# ECG-EEG.net
KiCad netlist of a schematic drawn in EAGLE
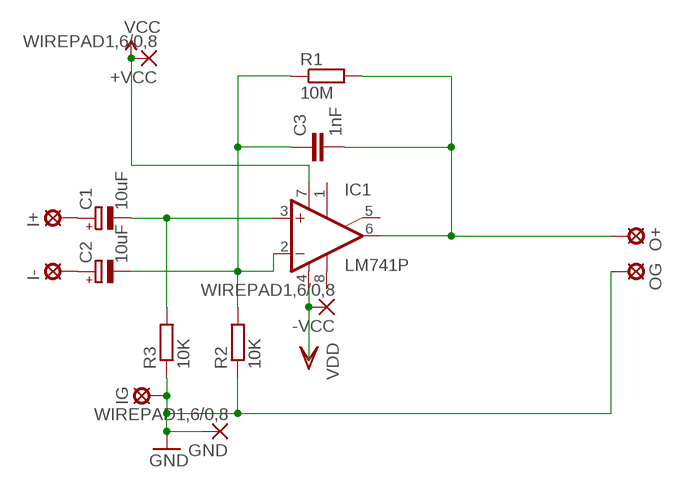
[diagram p0: schematic, sheet 1]

(export (version "E")
  (design (tool "Eeschema 10.0.6"))
  (components
    (comp (ref "+VCC")
      (value "WIREPAD1,6/0,8")
      (footprint "eagle-import:1,6_0,8")
      (libsource (lib "eagle-import") (part "WIREPAD1,6/0,8"))
    )
    (comp (ref "-VCC")
      (value "WIREPAD1,6/0,8")
      (footprint "eagle-import:1,6_0,8")
      (libsource (lib "eagle-import") (part "WIREPAD1,6/0,8"))
    )
    (comp (ref "C1")
      (value "10uF")
      (footprint "eagle-import:E1,8-4")
      (libsource (lib "eagle-import") (part "CPOL-EUE1.8-4"))
    )
    (comp (ref "C2")
      (value "10uF")
      (footprint "eagle-import:E1,8-4")
      (libsource (lib "eagle-import") (part "CPOL-EUE1.8-4"))
    )
    (comp (ref "C3")
      (value "1nF")
      (footprint "eagle-import:C025-025X050")
      (libsource (lib "eagle-import") (part "C-EU025-025X050"))
    )
    (comp (ref "GND")
      (value "WIREPAD1,6/0,8")
      (footprint "eagle-import:1,6_0,8")
      (libsource (lib "eagle-import") (part "WIREPAD1,6/0,8"))
    )
    (comp (ref "I+")
      (value "LSP10")
      (footprint "eagle-import:LSP10")
      (libsource (lib "eagle-import") (part "LSP10"))
    )
    (comp (ref "I-")
      (value "LSP10")
      (footprint "eagle-import:LSP10")
      (libsource (lib "eagle-import") (part "LSP10"))
    )
    (comp (ref "IC1")
      (value "LM741P")
      (footprint "eagle-import:DIL08")
      (libsource (lib "eagle-import") (part "741PLM"))
    )
    (comp (ref "IG")
      (value "LSP10")
      (footprint "eagle-import:LSP10")
      (libsource (lib "eagle-import") (part "LSP10"))
    )
    (comp (ref "O+")
      (value "LSP10")
      (footprint "eagle-import:LSP10")
      (libsource (lib "eagle-import") (part "LSP10"))
    )
    (comp (ref "OG")
      (value "LSP10")
      (footprint "eagle-import:LSP10")
      (libsource (lib "eagle-import") (part "LSP10"))
    )
    (comp (ref "R1")
      (value "10M")
      (footprint "eagle-import:0204_7")
      (libsource (lib "eagle-import") (part "R-EU_0204/7"))
    )
    (comp (ref "R2")
      (value "10K")
      (footprint "eagle-import:0204_7")
      (libsource (lib "eagle-import") (part "R-EU_0204/7"))
    )
    (comp (ref "R3")
      (value "10K")
      (footprint "eagle-import:0204_7")
      (libsource (lib "eagle-import") (part "R-EU_0204/7"))
    )
  )
  (nets
    (net (code "1") (name "GND") (class "Default")
      (node (ref "GND") (pin "1") (pinfunction "P_1") (pintype "passive"))
      (node (ref "IG") (pin "MP") (pinfunction "MP_MP") (pintype "passive"))
      (node (ref "OG") (pin "MP") (pinfunction "MP_MP") (pintype "passive"))
      (node (ref "R2") (pin "1") (pinfunction "1_1") (pintype "passive"))
      (node (ref "R3") (pin "1") (pinfunction "1_1") (pintype "passive"))
    )
    (net (code "2") (name "Net-(-VCC-P)") (class "Default")
      (node (ref "-VCC") (pin "1") (pinfunction "P_1") (pintype "passive"))
      (node (ref "IC1") (pin "4") (pinfunction "V-_4") (pintype "power_in"))
    )
    (net (code "3") (name "Net-(C1-Pad+)") (class "Default")
      (node (ref "C1") (pin "+") (pinfunction "+_+") (pintype "passive"))
      (node (ref "I+") (pin "MP") (pinfunction "MP_MP") (pintype "passive"))
    )
    (net (code "4") (name "Net-(C2-Pad+)") (class "Default")
      (node (ref "C2") (pin "+") (pinfunction "+_+") (pintype "passive"))
      (node (ref "I-") (pin "MP") (pinfunction "MP_MP") (pintype "passive"))
    )
    (net (code "5") (name "Net-(IC1-+IN)") (class "Default")
      (node (ref "C1") (pin "-") (pinfunction "-_-") (pintype "passive"))
      (node (ref "IC1") (pin "3") (pinfunction "+IN_3") (pintype "input"))
      (node (ref "R3") (pin "2") (pinfunction "2_2") (pintype "passive"))
    )
    (net (code "6") (name "Net-(IC1--IN)") (class "Default")
      (node (ref "C2") (pin "-") (pinfunction "-_-") (pintype "passive"))
      (node (ref "C3") (pin "1") (pinfunction "1_1") (pintype "passive"))
      (node (ref "IC1") (pin "2") (pinfunction "-IN_2") (pintype "input"))
      (node (ref "R1") (pin "1") (pinfunction "1_1") (pintype "passive"))
      (node (ref "R2") (pin "2") (pinfunction "2_2") (pintype "passive"))
    )
    (net (code "7") (name "Net-(IC1-OUT)") (class "Default")
      (node (ref "C3") (pin "2") (pinfunction "2_2") (pintype "passive"))
      (node (ref "IC1") (pin "6") (pinfunction "OUT_6") (pintype "output"))
      (node (ref "O+") (pin "MP") (pinfunction "MP_MP") (pintype "passive"))
      (node (ref "R1") (pin "2") (pinfunction "2_2") (pintype "passive"))
    )
    (net (code "8") (name "VCC") (class "Default")
      (node (ref "+VCC") (pin "1") (pinfunction "P_1") (pintype "passive"))
      (node (ref "IC1") (pin "7") (pinfunction "V+_7") (pintype "power_in"))
    )
    (net (code "10") (name "unconnected-(IC1-ON1-Pad1)") (class "Default")
      (node (ref "IC1") (pin "1") (pinfunction "ON1_1") (pintype "passive"))
    )
    (net (code "11") (name "unconnected-(IC1-ON2-Pad5)") (class "Default")
      (node (ref "IC1") (pin "5") (pinfunction "ON2_5") (pintype "passive"))
    )
    (net (code "12") (name "unconnected-(IC1-OPT-Pad8)") (class "Default")
      (node (ref "IC1") (pin "8") (pinfunction "OPT_8") (pintype "passive"))
    )
  )
)
